# Ethernet.net
KiCad netlist of a schematic drawn in Altium Designer
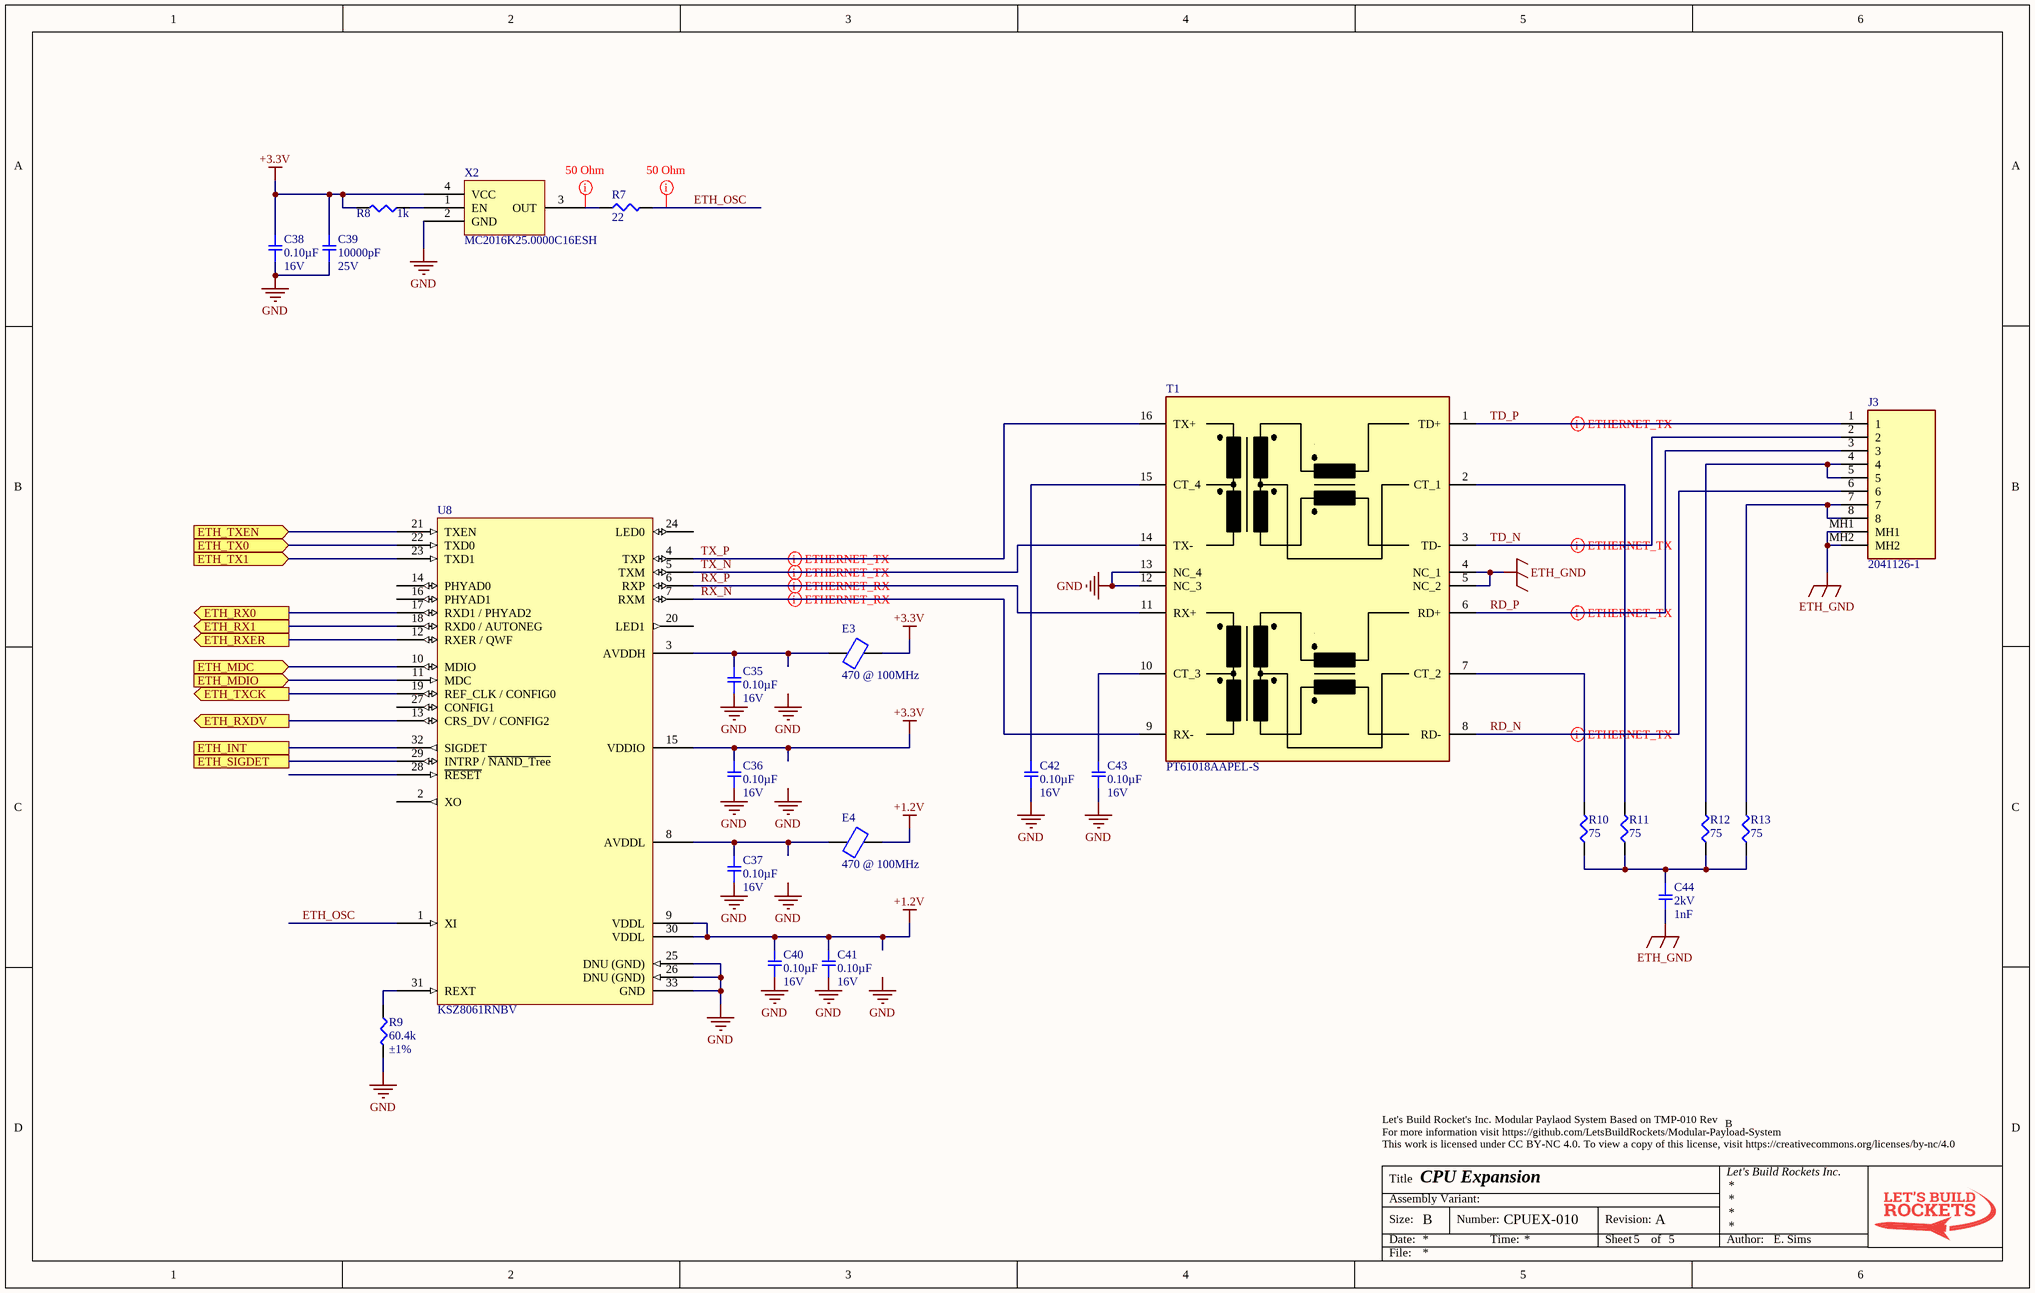
[diagram p0: Ethernet.SchDoc]

(export (version "E")
  (design (tool "Eeschema 10.0.6"))
  (components
    (comp (ref "C35")
      (value "0.10µF")
      (footprint "SMD-0402C")
      (description "CAP CER 0.1UF 16V X7R 0402")
      (fields
        (field (name "DIGI-KEY PART NUMBER") "490-4759-1-ND")
        (field (name "PART NUMBER") "GCM155R71C104KA55D")
        (field (name "VOLTAGE") "16V")
      )
      (libsource (lib "capacitor_murata_0402") (part "GCM155R71C104KA55D"))
    )
    (comp (ref "C36")
      (value "0.10µF")
      (footprint "SMD-0402C")
      (description "CAP CER 0.1UF 16V X7R 0402")
      (fields
        (field (name "DIGI-KEY PART NUMBER") "490-4759-1-ND")
        (field (name "PART NUMBER") "GCM155R71C104KA55D")
        (field (name "VOLTAGE") "16V")
      )
      (libsource (lib "capacitor_murata_0402") (part "GCM155R71C104KA55D"))
    )
    (comp (ref "C37")
      (value "0.10µF")
      (footprint "SMD-0402C")
      (description "CAP CER 0.1UF 16V X7R 0402")
      (fields
        (field (name "DIGI-KEY PART NUMBER") "490-4759-1-ND")
        (field (name "PART NUMBER") "GCM155R71C104KA55D")
        (field (name "VOLTAGE") "16V")
      )
      (libsource (lib "capacitor_murata_0402") (part "GCM155R71C104KA55D"))
    )
    (comp (ref "C38")
      (value "0.10µF")
      (footprint "SMD-0402C")
      (description "CAP CER 0.1UF 16V X7R 0402")
      (fields
        (field (name "DIGI-KEY PART NUMBER") "490-4759-1-ND")
        (field (name "PART NUMBER") "GCM155R71C104KA55D")
        (field (name "VOLTAGE") "16V")
      )
      (libsource (lib "capacitor_murata_0402") (part "GCM155R71C104KA55D"))
    )
    (comp (ref "C39")
      (value "10000pF")
      (footprint "SMD-0402C")
      (description "CAP CER 10000PF 25V X7R 0402")
      (fields
        (field (name "DIGI-KEY PART NUMBER") "490-6043-1-ND")
        (field (name "PART NUMBER") "GCM155R71E103KA37D")
        (field (name "VOLTAGE") "25V")
      )
      (libsource (lib "capacitor_murata_0402") (part "GCM155R71E103KA37D"))
    )
    (comp (ref "C40")
      (value "0.10µF")
      (footprint "SMD-0402C")
      (description "CAP CER 0.1UF 16V X7R 0402")
      (fields
        (field (name "DIGI-KEY PART NUMBER") "490-4759-1-ND")
        (field (name "PART NUMBER") "GCM155R71C104KA55D")
        (field (name "VOLTAGE") "16V")
      )
      (libsource (lib "capacitor_murata_0402") (part "GCM155R71C104KA55D"))
    )
    (comp (ref "C41")
      (value "0.10µF")
      (footprint "SMD-0402C")
      (description "CAP CER 0.1UF 16V X7R 0402")
      (fields
        (field (name "DIGI-KEY PART NUMBER") "490-4759-1-ND")
        (field (name "PART NUMBER") "GCM155R71C104KA55D")
        (field (name "VOLTAGE") "16V")
      )
      (libsource (lib "capacitor_murata_0402") (part "GCM155R71C104KA55D"))
    )
    (comp (ref "C42")
      (value "0.10µF")
      (footprint "SMD-0402C")
      (description "CAP CER 0.1UF 16V X7R 0402")
      (fields
        (field (name "DIGI-KEY PART NUMBER") "490-4759-1-ND")
        (field (name "PART NUMBER") "GCM155R71C104KA55D")
        (field (name "VOLTAGE") "16V")
      )
      (libsource (lib "capacitor_murata_0402") (part "GCM155R71C104KA55D"))
    )
    (comp (ref "C43")
      (value "0.10µF")
      (footprint "SMD-0402C")
      (description "CAP CER 0.1UF 16V X7R 0402")
      (fields
        (field (name "DIGI-KEY PART NUMBER") "490-4759-1-ND")
        (field (name "PART NUMBER") "GCM155R71C104KA55D")
        (field (name "VOLTAGE") "16V")
      )
      (libsource (lib "capacitor_murata_0402") (part "GCM155R71C104KA55D"))
    )
    (comp (ref "C44")
      (value "1nF")
      (footprint "SMD-1206C")
      (fields (field (name "VOLTAGE") "2kV") (field (name "Comment") "C1206C102KGRACAUTO"))
      (libsource (lib "KEMET") (part "C1206C102KGRACAUTO"))
    )
    (comp (ref "E3")
      (value "470 @ 100MHz")
      (fields (field (name "Comment") "MPZ1608S471ATD25"))
      (libsource (lib "ModularPayload") (part "MPZ1608S471ATD25"))
    )
    (comp (ref "E4")
      (value "470 @ 100MHz")
      (fields (field (name "Comment") "MPZ1608S471ATD25"))
      (libsource (lib "ModularPayload") (part "MPZ1608S471ATD25"))
    )
    (comp (ref "J3")
      (value "2041126-1")
      (footprint "TE_2041126-1")
      (description "Connector")
      (libsource (lib "ModularPayload") (part "2041126-1"))
    )
    (comp (ref "R7")
      (value "22")
      (footprint "SMD-0402-RES")
      (description "RES SMD 22 OHM 1% 1/10W 0402")
      (fields
        (field (name "PART NUMBER") "ERJ-2RKF22R0X")
        (field (name "DIGI-KEY PART NUMBER") "P22.0LCT-ND")
      )
      (libsource (lib "Panasonic_ERJ_0402") (part "ERJ-2RKF22R0X"))
    )
    (comp (ref "R8")
      (value "1k")
      (footprint "SMD-0402-RES")
      (description "RES SMD 1K OHM 5% 1/10W 0402")
      (fields (field (name "PART NUMBER") "ERJ-2GEJ102X") (field (name "DIGI-KEY PART NUMBER") "P1.0KJCT-ND"))
      (libsource (lib "Panasonic_ERJ_0402") (part "ERJ-2GEJ102X"))
    )
    (comp (ref "R9")
      (value "60.4k")
      (footprint "SMD-0402-RES")
      (description "RES SMD 60.4K OHM 1% 1/10W 0402")
      (fields
        (field (name "PART NUMBER") "ERJ-2RKF6042X")
        (field (name "DIGI-KEY PART NUMBER") "P60.4KLCT-ND")
        (field (name "TOLERANCE") "±1%")
      )
      (libsource (lib "Panasonic_ERJ_0402") (part "ERJ-2RKF6042X"))
    )
    (comp (ref "R10")
      (value "75")
      (footprint "SMD-0402-RES")
      (description "RES SMD 75 OHM 5% 1/10W 0402")
      (fields (field (name "PART NUMBER") "ERJ-2GEJ750X") (field (name "DIGI-KEY PART NUMBER") "P75JCT-ND"))
      (libsource (lib "Panasonic_ERJ_0402") (part "ERJ-2GEJ750X"))
    )
    (comp (ref "R11")
      (value "75")
      (footprint "SMD-0402-RES")
      (description "RES SMD 75 OHM 5% 1/10W 0402")
      (fields (field (name "PART NUMBER") "ERJ-2GEJ750X") (field (name "DIGI-KEY PART NUMBER") "P75JCT-ND"))
      (libsource (lib "Panasonic_ERJ_0402") (part "ERJ-2GEJ750X"))
    )
    (comp (ref "R12")
      (value "75")
      (footprint "SMD-0402-RES")
      (description "RES SMD 75 OHM 5% 1/10W 0402")
      (fields (field (name "PART NUMBER") "ERJ-2GEJ750X") (field (name "DIGI-KEY PART NUMBER") "P75JCT-ND"))
      (libsource (lib "Panasonic_ERJ_0402") (part "ERJ-2GEJ750X"))
    )
    (comp (ref "R13")
      (value "75")
      (footprint "SMD-0402-RES")
      (description "RES SMD 75 OHM 5% 1/10W 0402")
      (fields (field (name "PART NUMBER") "ERJ-2GEJ750X") (field (name "DIGI-KEY PART NUMBER") "P75JCT-ND"))
      (libsource (lib "Panasonic_ERJ_0402") (part "ERJ-2GEJ750X"))
    )
    (comp (ref "T1")
      (value "PT61018AAPEL-S")
      (footprint "SOIC127P930X590-16N")
      (description "Transformer")
      (libsource (lib "ModularPayload") (part "PT61018AAPEL-S"))
    )
    (comp (ref "U8")
      (value "KSZ8061RNBV")
      (footprint "QFN50P500X500X90_HS-33N (KSZ8061RNBV)")
      (libsource (lib "ModularPayload") (part "KSZ8061RNBV"))
    )
    (comp (ref "X2")
      (value "MC2016K25.0000C16ESH")
      (footprint "MC2016")
      (libsource (lib "ModularPayload") (part "MC2016K25.0000C16ESH"))
    )
  )
  (nets
    (net (code "1") (name "+1.2V") (class "Default")
      (node (ref "C40") (pin "2") (pinfunction "2_2") (pintype "passive"))
      (node (ref "C41") (pin "2") (pinfunction "2_2") (pintype "passive"))
      (node (ref "E4") (pin "2") (pinfunction "2_2") (pintype "passive"))
      (node (ref "U8") (pin "30") (pinfunction "VDDL_30") (pintype "power_in"))
      (node (ref "U8") (pin "9") (pinfunction "VDDL_9") (pintype "power_in"))
    )
    (net (code "2") (name "+3.3V") (class "Default")
      (node (ref "C36") (pin "2") (pinfunction "2_2") (pintype "passive"))
      (node (ref "C38") (pin "2") (pinfunction "2_2") (pintype "passive"))
      (node (ref "C39") (pin "2") (pinfunction "2_2") (pintype "passive"))
      (node (ref "E3") (pin "2") (pinfunction "2_2") (pintype "passive"))
      (node (ref "R8") (pin "2") (pinfunction "2_2") (pintype "passive"))
      (node (ref "U8") (pin "15") (pinfunction "VDDIO_15") (pintype "power_in"))
      (node (ref "X2") (pin "4") (pinfunction "VCC_4") (pintype "passive"))
    )
    (net (code "3") (name "/ETH_INT") (class "Default")
      (node (ref "U8") (pin "32") (pinfunction "SIGDET_32") (pintype "output"))
    )
    (net (code "4") (name "/ETH_MDC") (class "Default")
      (node (ref "U8") (pin "10") (pinfunction "MDIO_10") (pintype "bidirectional"))
    )
    (net (code "5") (name "/ETH_MDIO") (class "Default")
      (node (ref "U8") (pin "11") (pinfunction "MDC_11") (pintype "input"))
    )
    (net (code "6") (name "/ETH_OSC") (class "Default")
      (node (ref "R7") (pin "2") (pinfunction "2_2") (pintype "passive"))
      (node (ref "U8") (pin "1") (pinfunction "XI_1") (pintype "input"))
    )
    (net (code "7") (name "/ETH_RX0") (class "Default")
      (node (ref "U8") (pin "17") (pinfunction "RXD1_/_PHYAD2_17") (pintype "bidirectional"))
    )
    (net (code "8") (name "/ETH_RX1") (class "Default")
      (node (ref "U8") (pin "18") (pinfunction "RXD0_/_AUTONEG_18") (pintype "bidirectional"))
    )
    (net (code "9") (name "/ETH_RXDV") (class "Default")
      (node (ref "U8") (pin "13") (pinfunction "CRS_DV_/_CONFIG2_13") (pintype "bidirectional"))
    )
    (net (code "10") (name "/ETH_RXER") (class "Default")
      (node (ref "U8") (pin "12") (pinfunction "RXER_/_QWF_12") (pintype "bidirectional"))
    )
    (net (code "11") (name "/ETH_SIGDET") (class "Default")
      (node (ref "U8") (pin "29") (pinfunction "INTRP_/_~{NAND_Tree}_29") (pintype "bidirectional"))
    )
    (net (code "12") (name "/ETH_TX0") (class "Default")
      (node (ref "U8") (pin "22") (pinfunction "TXD0_22") (pintype "input"))
    )
    (net (code "13") (name "/ETH_TX1") (class "Default")
      (node (ref "U8") (pin "23") (pinfunction "TXD1_23") (pintype "input"))
    )
    (net (code "14") (name "/ETH_TXCK") (class "Default")
      (node (ref "U8") (pin "19") (pinfunction "REF_CLK_/_CONFIG0_19") (pintype "bidirectional"))
    )
    (net (code "15") (name "/ETH_TXEN") (class "Default")
      (node (ref "U8") (pin "21") (pinfunction "TXEN_21") (pintype "input"))
    )
    (net (code "16") (name "/RD_N") (class "Default")
      (node (ref "J3") (pin "6") (pinfunction "6_6") (pintype "passive"))
      (node (ref "T1") (pin "8") (pinfunction "RD-_8") (pintype "passive"))
    )
    (net (code "17") (name "/RD_P") (class "Default")
      (node (ref "J3") (pin "3") (pinfunction "3_3") (pintype "passive"))
      (node (ref "T1") (pin "6") (pinfunction "RD+_6") (pintype "passive"))
    )
    (net (code "18") (name "/RX_N") (class "Default")
      (node (ref "T1") (pin "9") (pinfunction "RX-_9") (pintype "passive"))
      (node (ref "U8") (pin "7") (pinfunction "RXM_7") (pintype "bidirectional"))
    )
    (net (code "19") (name "/RX_P") (class "Default")
      (node (ref "T1") (pin "11") (pinfunction "RX+_11") (pintype "passive"))
      (node (ref "U8") (pin "6") (pinfunction "RXP_6") (pintype "bidirectional"))
    )
    (net (code "20") (name "/TD_N") (class "Default")
      (node (ref "J3") (pin "2") (pinfunction "2_2") (pintype "passive"))
      (node (ref "T1") (pin "3") (pinfunction "TD-_3") (pintype "passive"))
    )
    (net (code "21") (name "/TD_P") (class "Default")
      (node (ref "J3") (pin "1") (pinfunction "1_1") (pintype "passive"))
      (node (ref "T1") (pin "1") (pinfunction "TD+_1") (pintype "passive"))
    )
    (net (code "22") (name "/TX_N") (class "Default")
      (node (ref "T1") (pin "14") (pinfunction "TX-_14") (pintype "passive"))
      (node (ref "U8") (pin "5") (pinfunction "TXM_5") (pintype "bidirectional"))
    )
    (net (code "23") (name "/TX_P") (class "Default")
      (node (ref "T1") (pin "16") (pinfunction "TX+_16") (pintype "passive"))
      (node (ref "U8") (pin "4") (pinfunction "TXP_4") (pintype "bidirectional"))
    )
    (net (code "24") (name "ETH_GND") (class "Default")
      (node (ref "C44") (pin "2") (pinfunction "2_2") (pintype "passive"))
      (node (ref "J3") (pin "MH1") (pinfunction "MH1_MH1") (pintype "passive"))
      (node (ref "J3") (pin "MH2") (pinfunction "MH2_MH2") (pintype "passive"))
      (node (ref "T1") (pin "4") (pinfunction "NC_1_4") (pintype "passive"))
      (node (ref "T1") (pin "5") (pinfunction "NC_2_5") (pintype "passive"))
    )
    (net (code "25") (name "GND") (class "Default")
      (node (ref "C35") (pin "1") (pinfunction "1_1") (pintype "passive"))
      (node (ref "C36") (pin "1") (pinfunction "1_1") (pintype "passive"))
      (node (ref "C37") (pin "1") (pinfunction "1_1") (pintype "passive"))
      (node (ref "C38") (pin "1") (pinfunction "1_1") (pintype "passive"))
      (node (ref "C39") (pin "1") (pinfunction "1_1") (pintype "passive"))
      (node (ref "C40") (pin "1") (pinfunction "1_1") (pintype "passive"))
      (node (ref "C41") (pin "1") (pinfunction "1_1") (pintype "passive"))
      (node (ref "C42") (pin "1") (pinfunction "1_1") (pintype "passive"))
      (node (ref "C43") (pin "1") (pinfunction "1_1") (pintype "passive"))
      (node (ref "R9") (pin "2") (pinfunction "2_2") (pintype "passive"))
      (node (ref "T1") (pin "12") (pinfunction "NC_3_12") (pintype "passive"))
      (node (ref "T1") (pin "13") (pinfunction "NC_4_13") (pintype "passive"))
      (node (ref "U8") (pin "25") (pinfunction "DNU_(GND)_25") (pintype "input"))
      (node (ref "U8") (pin "26") (pinfunction "DNU_(GND)_26") (pintype "input"))
      (node (ref "U8") (pin "33") (pinfunction "GND_33") (pintype "power_in"))
      (node (ref "X2") (pin "2") (pinfunction "GND_2") (pintype "passive"))
    )
    (net (code "26") (name "Net-(C44-Pad1)") (class "Default")
      (node (ref "C44") (pin "1") (pinfunction "1_1") (pintype "passive"))
      (node (ref "R10") (pin "1") (pinfunction "1_1") (pintype "passive"))
      (node (ref "R11") (pin "1") (pinfunction "1_1") (pintype "passive"))
      (node (ref "R12") (pin "1") (pinfunction "1_1") (pintype "passive"))
      (node (ref "R13") (pin "1") (pinfunction "1_1") (pintype "passive"))
    )
    (net (code "27") (name "Net-(J3-Pad4)") (class "Default")
      (node (ref "J3") (pin "4") (pinfunction "4_4") (pintype "passive"))
      (node (ref "J3") (pin "5") (pinfunction "5_5") (pintype "passive"))
      (node (ref "R12") (pin "2") (pinfunction "2_2") (pintype "passive"))
    )
    (net (code "28") (name "Net-(J3-Pad7)") (class "Default")
      (node (ref "J3") (pin "7") (pinfunction "7_7") (pintype "passive"))
      (node (ref "J3") (pin "8") (pinfunction "8_8") (pintype "passive"))
      (node (ref "R13") (pin "2") (pinfunction "2_2") (pintype "passive"))
    )
    (net (code "29") (name "Net-(T1-CT_1)") (class "Default")
      (node (ref "R11") (pin "2") (pinfunction "2_2") (pintype "passive"))
      (node (ref "T1") (pin "2") (pinfunction "CT_1_2") (pintype "passive"))
    )
    (net (code "30") (name "Net-(T1-CT_2)") (class "Default")
      (node (ref "R10") (pin "2") (pinfunction "2_2") (pintype "passive"))
      (node (ref "T1") (pin "7") (pinfunction "CT_2_7") (pintype "passive"))
    )
    (net (code "31") (name "Net-(T1-CT_3)") (class "Default")
      (node (ref "C43") (pin "2") (pinfunction "2_2") (pintype "passive"))
      (node (ref "T1") (pin "10") (pinfunction "CT_3_10") (pintype "passive"))
    )
    (net (code "32") (name "Net-(T1-CT_4)") (class "Default")
      (node (ref "C42") (pin "2") (pinfunction "2_2") (pintype "passive"))
      (node (ref "T1") (pin "15") (pinfunction "CT_4_15") (pintype "passive"))
    )
    (net (code "33") (name "Net-(U8-AVDDH)") (class "Default")
      (node (ref "C35") (pin "2") (pinfunction "2_2") (pintype "passive"))
      (node (ref "E3") (pin "1") (pinfunction "1_1") (pintype "passive"))
      (node (ref "U8") (pin "3") (pinfunction "AVDDH_3") (pintype "power_in"))
    )
    (net (code "34") (name "Net-(U8-AVDDL)") (class "Default")
      (node (ref "C37") (pin "2") (pinfunction "2_2") (pintype "passive"))
      (node (ref "E4") (pin "1") (pinfunction "1_1") (pintype "passive"))
      (node (ref "U8") (pin "8") (pinfunction "AVDDL_8") (pintype "power_in"))
    )
    (net (code "35") (name "Net-(U8-REXT)") (class "Default")
      (node (ref "R9") (pin "1") (pinfunction "1_1") (pintype "passive"))
      (node (ref "U8") (pin "31") (pinfunction "REXT_31") (pintype "input"))
    )
    (net (code "36") (name "Net-(X2-EN)") (class "Default")
      (node (ref "R8") (pin "1") (pinfunction "1_1") (pintype "passive"))
      (node (ref "X2") (pin "1") (pinfunction "EN_1") (pintype "passive"))
    )
    (net (code "37") (name "Net-(X2-OUT)") (class "Default")
      (node (ref "R7") (pin "1") (pinfunction "1_1") (pintype "passive"))
      (node (ref "X2") (pin "3") (pinfunction "OUT_3") (pintype "passive"))
    )
    (net (code "38") (name "unconnected-(U8-CONFIG1-Pad27)") (class "Default")
      (node (ref "U8") (pin "27") (pinfunction "CONFIG1_27") (pintype "bidirectional"))
    )
    (net (code "39") (name "unconnected-(U8-LED0-Pad24)") (class "Default")
      (node (ref "U8") (pin "24") (pinfunction "LED0_24") (pintype "bidirectional"))
    )
    (net (code "40") (name "unconnected-(U8-LED1-Pad20)") (class "Default")
      (node (ref "U8") (pin "20") (pinfunction "LED1_20") (pintype "output"))
    )
    (net (code "41") (name "unconnected-(U8-PHYAD0-Pad14)") (class "Default")
      (node (ref "U8") (pin "14") (pinfunction "PHYAD0_14") (pintype "bidirectional"))
    )
    (net (code "42") (name "unconnected-(U8-PHYAD1-Pad16)") (class "Default")
      (node (ref "U8") (pin "16") (pinfunction "PHYAD1_16") (pintype "bidirectional"))
    )
    (net (code "43") (name "unconnected-(U8-XO-Pad2)") (class "Default")
      (node (ref "U8") (pin "2") (pinfunction "XO_2") (pintype "output"))
    )
    (net (code "44") (name "unconnected-(U8-~{RESET}-Pad28)") (class "Default")
      (node (ref "U8") (pin "28") (pinfunction "~{RESET}_28") (pintype "input"))
    )
  )
)
